# Sheet1.net
KiCad netlist of a schematic drawn in Altium Designer
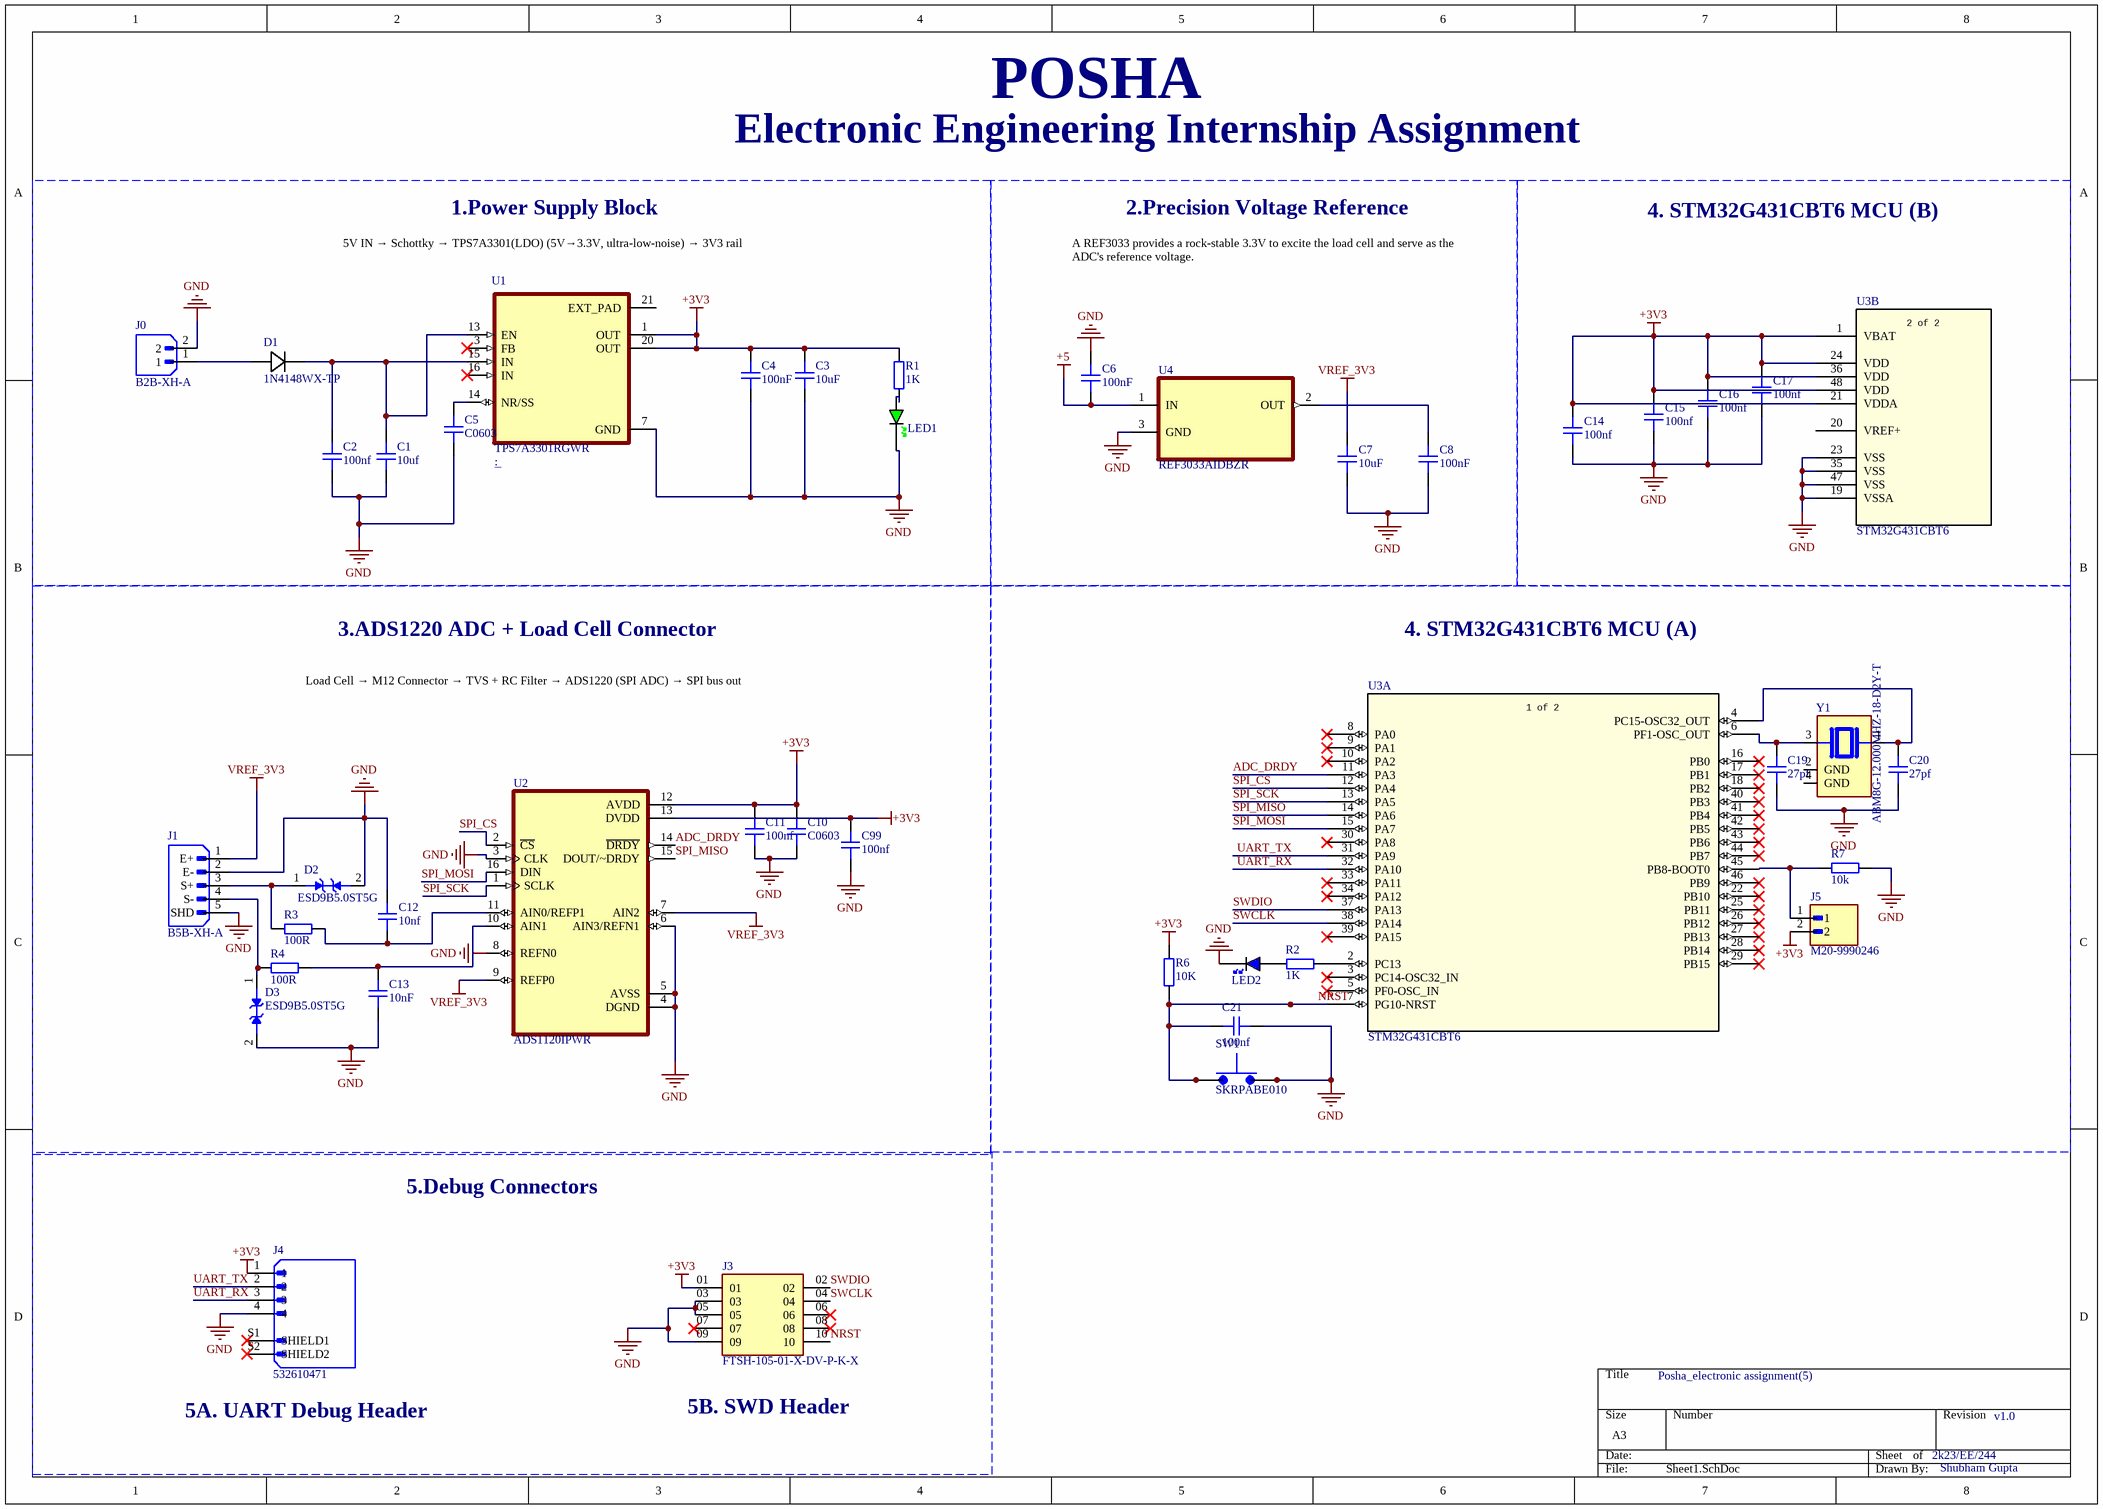
[diagram p0: Sheet1.SchDoc]

(export (version "E")
  (design (tool "Eeschema 10.0.6"))
  (components
    (comp (ref "C1")
      (value "10uf")
      (footprint "CAP_0805")
      (description "Capacitor SMD 0805")
      (libsource (lib "Schlib1") (part "CAP_0805"))
    )
    (comp (ref "C2")
      (value "100nf")
      (footprint "CAP_0603")
      (description "Capacitor SMD 0603")
      (libsource (lib "Schlib1") (part "CAP_0603"))
    )
    (comp (ref "C3")
      (value "10uF")
      (footprint "CAP_0603")
      (description "Capacitor SMD 0603")
      (libsource (lib "Schlib1") (part "CAP_0603"))
    )
    (comp (ref "C4")
      (value "100nF")
      (footprint "CAP_0805")
      (description "Capacitor SMD 0805")
      (libsource (lib "Schlib1") (part "CAP_0805"))
    )
    (comp (ref "C5")
      (value "C0603")
      (footprint "CAP_0603")
      (description "Capacitor SMD 0603")
      (libsource (lib "Schlib1") (part "CAP_0603"))
    )
    (comp (ref "C6")
      (value "100nF")
      (footprint "CAP_0603")
      (description "Capacitor SMD 0603")
      (libsource (lib "Schlib1") (part "CAP_0603"))
    )
    (comp (ref "C7")
      (value "10uF")
      (footprint "CAP_0805")
      (description "Capacitor SMD 0805")
      (libsource (lib "Schlib1") (part "CAP_0805"))
    )
    (comp (ref "C8")
      (value "100nF")
      (footprint "CAP_0603")
      (description "Capacitor SMD 0603")
      (libsource (lib "Schlib1") (part "CAP_0603"))
    )
    (comp (ref "C10")
      (value "C0603")
      (footprint "CAP_0603")
      (description "Capacitor SMD 0603")
      (libsource (lib "Schlib1") (part "CAP_0603"))
    )
    (comp (ref "C11")
      (value "100nf")
      (footprint "CAP_0603")
      (description "Capacitor SMD 0603")
      (libsource (lib "Schlib1") (part "CAP_0603"))
    )
    (comp (ref "C12")
      (value "10nf")
      (footprint "CAP_0603")
      (description "Capacitor SMD 0603")
      (libsource (lib "Schlib1") (part "CAP_0603"))
    )
    (comp (ref "C13")
      (value "10nF")
      (footprint "CAP_0603")
      (description "Capacitor SMD 0603")
      (libsource (lib "Schlib1") (part "CAP_0603"))
    )
    (comp (ref "C14")
      (value "100nf")
      (footprint "CAP_0603")
      (description "Capacitor SMD 0603")
      (libsource (lib "Schlib1") (part "CAP_0603"))
    )
    (comp (ref "C15")
      (value "100nf")
      (footprint "CAP_0603")
      (description "Capacitor SMD 0603")
      (libsource (lib "Schlib1") (part "CAP_0603"))
    )
    (comp (ref "C16")
      (value "100nf")
      (footprint "CAP_0603")
      (description "Capacitor SMD 0603")
      (libsource (lib "Schlib1") (part "CAP_0603"))
    )
    (comp (ref "C17")
      (value "100nf")
      (footprint "CAP_0603")
      (description "Capacitor SMD 0603")
      (libsource (lib "Schlib1") (part "CAP_0603"))
    )
    (comp (ref "C19")
      (value "27pf")
      (footprint "CAP_0603")
      (description "Capacitor SMD 0603")
      (libsource (lib "Schlib1") (part "CAP_0603"))
    )
    (comp (ref "C20")
      (value "27pf")
      (footprint "CAP_0603")
      (description "Capacitor SMD 0603")
      (libsource (lib "Schlib1") (part "CAP_0603"))
    )
    (comp (ref "C21")
      (value "100nf")
      (footprint "CAP_0603")
      (description "Capacitor SMD 0603")
      (libsource (lib "Schlib1") (part "CAP_0603"))
    )
    (comp (ref "C99")
      (value "100nf")
      (footprint "CAP_0603")
      (description "Capacitor SMD 0603")
      (libsource (lib "Schlib1") (part "CAP_0603"))
    )
    (comp (ref "D1")
      (value "1N4148WX-TP")
      (footprint "CR_SOD323_MCC")
      (description "Description")
      (fields (field (name "COPYRIGHT") "Copyright (C) 2025 Ultra Librarian. All rights reserved."))
      (libsource (lib "Schlib1") (part "1N4148WX-TP"))
    )
    (comp (ref "D2")
      (value "ESD9B5.0ST5G")
      (footprint "SODFL1006X40N")
      (description "Clamp Ipp Tvs Diode Surface Mount SOD-923")
      (fields (field (name "MF") "ON Semiconductor"))
      (libsource (lib "Schlib1") (part "ESD9B5.0ST5G"))
    )
    (comp (ref "D3")
      (value "ESD9B5.0ST5G")
      (footprint "SODFL1006X40N")
      (description "Clamp Ipp Tvs Diode Surface Mount SOD-923")
      (fields (field (name "MF") "ON Semiconductor"))
      (libsource (lib "Schlib1") (part "ESD9B5.0ST5G"))
    )
    (comp (ref "J0")
      (value "B2B-XH-A")
      (footprint "HARWIN_M20-9990246")
      (fields (field (name "MF") "{'manufacturer': u'JST Sales America Inc.'}"))
      (libsource (lib "Schlib1") (part "B2B-XH-A"))
    )
    (comp (ref "J1")
      (value "B5B-XH-A")
      (footprint "JST_B5B-XH-A")
      (description "Connector Header Through Hole 5 position 0.098 (2.50mm)")
      (fields (field (name "MF") "JST Sales"))
      (libsource (lib "Schlib1") (part "B5B-XH-A"))
    )
    (comp (ref "J3")
      (value "FTSH-105-01-X-DV-P-K-X")
      (footprint "SAMTEC_FTSH-105-01-X-DV-P-K-X")
      (fields (field (name "MF") "{'manufacturer': u'Samtec Inc.'}"))
      (libsource (lib "Schlib1") (part "FTSH-105-01-X-DV-P-K-X"))
    )
    (comp (ref "J4")
      (value "532610471")
      (footprint "MOLEX_532610471")
      (description "Connector Header Surface Mount, Right Angle 4 position 0.049 (1.25mm)")
      (fields (field (name "MF") "Molex"))
      (libsource (lib "Schlib1") (part "532610471"))
    )
    (comp (ref "J5")
      (value "M20-9990246")
      (footprint "HARWIN_M20-9990246")
      (description "2.54mm (0.1) Pitch SIL Vertical Throughboard Pin Header, 6.1mm mating pin height, tin, 2 contacts")
      (fields (field (name "MF") "Harwin"))
      (libsource (lib "Schlib1") (part "M20-9990246"))
    )
    (comp (ref "LED1")
      (value "GREEN")
      (footprint "LED_0603_GREEN")
      (description "LED 0603 GREEN SMD")
      (libsource (lib "Schlib1") (part "LED_0603_GREEN"))
    )
    (comp (ref "LED2")
      (value "BLUE")
      (footprint "LED_0402_BLUE")
      (description "LED 0402 BLUE SMD")
      (libsource (lib "Schlib1") (part "LED_0402_BLUE"))
    )
    (comp (ref "R1")
      (value "1K")
      (footprint "RES_0603")
      (description "Resistor SMD 0603")
      (libsource (lib "Schlib1") (part "RES_0603"))
    )
    (comp (ref "R2")
      (value "1K")
      (footprint "RES_0603")
      (description "Resistor SMD 0603")
      (libsource (lib "Schlib1") (part "RES_0603"))
    )
    (comp (ref "R3")
      (value "100R")
      (footprint "RES_0603")
      (description "Resistor SMD 0603")
      (libsource (lib "Schlib1") (part "RES_0603"))
    )
    (comp (ref "R4")
      (value "100R")
      (footprint "RES_0603")
      (description "Resistor SMD 0603")
      (libsource (lib "Schlib1") (part "RES_0603"))
    )
    (comp (ref "R6")
      (value "10K")
      (footprint "RES_0603")
      (description "Resistor SMD 0603")
      (libsource (lib "Schlib1") (part "RES_0603"))
    )
    (comp (ref "R7")
      (value "10k")
      (footprint "RES_0603")
      (description "Resistor SMD 0603")
      (libsource (lib "Schlib1") (part "RES_0603"))
    )
    (comp (ref "SW1")
      (value "SKRPABE010")
      (footprint "SW_SKRPABE010")
      (description "Switch Tactile N.O. SPST Button J-Bend 0.05A 16VDC 1.57N SMD Automotive T/R")
      (fields (field (name "MF") "ALPS"))
      (libsource (lib "Schlib1") (part "SKRPABE010"))
    )
    (comp (ref "U1")
      (value "TPS7A3301RGWR")
      (footprint "QFN65P500X500X100-21N")
      (description "1-A, high-PSRR, negative, adjustable low-dropout voltage regulator with enable 20-VQFN -40 to 125")
      (fields (field (name "DIGI-KEY_PART_NUMBER") "296-39502-1-ND") (field (name "MF") "Texas Instruments"))
      (libsource (lib "Schlib1") (part "TPS7A3301RGWR"))
    )
    (comp (ref "U2")
      (value "ADS1120IPWR")
      (footprint "SOP65P640X120-16N")
      (fields (field (name "MF") "Texas Instruments"))
      (libsource (lib "Schlib1") (part "ADS1120IPWR"))
    )
    (comp (ref "U3")
      (value "STM32G431CBT6")
      (footprint "LQFP48-7x7mm")
      (fields (field (name "COPYRIGHT") "Copyright (C) 2025 Ultra Librarian. All rights reserved."))
      (libsource (lib "Schlib1") (part "STM32G431CBT6"))
    )
    (comp (ref "U4")
      (value "REF3033AIDBZR")
      (footprint "SOT95P237X112-3N")
      (description "3.3-V, 50-ppm/Â°C, 50-ÂµA in 3-pin SOT-23 package series (bandgap) voltage reference")
      (fields (field (name "MF") "Texas Instruments"))
      (libsource (lib "Schlib1") (part "REF3033AIDBZR"))
    )
    (comp (ref "Y1")
      (value "ABM8G-12.000MHZ-18-D2Y-T")
      (footprint "XTAL_ABM8G-12.000MHZ-18-D2Y-T")
      (description "12 MHz Â±20ppm Crystal 18pF 120 Ohms 4-SMD, No Lead")
      (fields (field (name "DIGI-KEY_PART_NUMBER") "535-10261-2-ND") (field (name "MF") "Abracon"))
      (libsource (lib "Schlib1") (part "ABM8G-12.000MHZ-18-D2Y-T"))
    )
  )
  (nets
    (net (code "1") (name "+3V3") (class "Default")
      (node (ref "C10") (pin "2") (pinfunction "2_2") (pintype "passive"))
      (node (ref "C11") (pin "2") (pinfunction "2_2") (pintype "passive"))
      (node (ref "C14") (pin "2") (pinfunction "2_2") (pintype "passive"))
      (node (ref "C15") (pin "2") (pinfunction "2_2") (pintype "passive"))
      (node (ref "C16") (pin "2") (pinfunction "2_2") (pintype "passive"))
      (node (ref "C17") (pin "2") (pinfunction "2_2") (pintype "passive"))
      (node (ref "C3") (pin "2") (pinfunction "2_2") (pintype "passive"))
      (node (ref "C4") (pin "2") (pinfunction "2_2") (pintype "passive"))
      (node (ref "C99") (pin "2") (pinfunction "2_2") (pintype "passive"))
      (node (ref "J3") (pin "01") (pinfunction "01_01") (pintype "passive"))
      (node (ref "J4") (pin "1") (pinfunction "1_1") (pintype "passive"))
      (node (ref "J5") (pin "2") (pinfunction "2_2") (pintype "passive"))
      (node (ref "R1") (pin "2") (pinfunction "2_2") (pintype "passive"))
      (node (ref "R6") (pin "2") (pinfunction "2_2") (pintype "passive"))
      (node (ref "U1") (pin "1") (pinfunction "OUT_1") (pintype "passive"))
      (node (ref "U1") (pin "20") (pinfunction "OUT_20") (pintype "passive"))
      (node (ref "U2") (pin "12") (pinfunction "AVDD_12") (pintype "power_in"))
      (node (ref "U2") (pin "13") (pinfunction "DVDD_13") (pintype "power_in"))
      (node (ref "U3") (pin "1") (pinfunction "VBAT_1") (pintype "power_in"))
      (node (ref "U3") (pin "21") (pinfunction "VDDA_21") (pintype "power_in"))
      (node (ref "U3") (pin "24") (pinfunction "VDD_24") (pintype "power_in"))
      (node (ref "U3") (pin "36") (pinfunction "VDD_36") (pintype "power_in"))
      (node (ref "U3") (pin "48") (pinfunction "VDD_48") (pintype "power_in"))
    )
    (net (code "2") (name "+5") (class "Default")
      (node (ref "C6") (pin "1") (pinfunction "1_1") (pintype "passive"))
      (node (ref "U4") (pin "1") (pinfunction "IN_1") (pintype "power_in"))
    )
    (net (code "3") (name "/ADC_DRDY") (class "Default")
      (node (ref "U2") (pin "14") (pinfunction "~{DRDY}_14") (pintype "output"))
      (node (ref "U3") (pin "11") (pinfunction "PA3_11") (pintype "bidirectional"))
    )
    (net (code "4") (name "/NRST") (class "Default")
      (node (ref "C21") (pin "2") (pinfunction "2_2") (pintype "passive"))
      (node (ref "J3") (pin "10") (pinfunction "10_10") (pintype "passive"))
      (node (ref "R6") (pin "1") (pinfunction "1_1") (pintype "passive"))
      (node (ref "SW1") (pin "1") (pinfunction "1_1") (pintype "passive"))
      (node (ref "SW1") (pin "2") (pinfunction "1_2") (pintype "passive"))
      (node (ref "U3") (pin "7") (pinfunction "PG10-NRST_7") (pintype "bidirectional"))
    )
    (net (code "5") (name "/SPI_CS") (class "Default")
      (node (ref "U2") (pin "2") (pinfunction "~{CS}_2") (pintype "input"))
      (node (ref "U3") (pin "12") (pinfunction "PA4_12") (pintype "bidirectional"))
    )
    (net (code "6") (name "/SPI_MISO") (class "Default")
      (node (ref "U2") (pin "15") (pinfunction "DOUT/~DRDY_15") (pintype "output"))
      (node (ref "U3") (pin "14") (pinfunction "PA6_14") (pintype "bidirectional"))
    )
    (net (code "7") (name "/SPI_MOSI") (class "Default")
      (node (ref "U2") (pin "16") (pinfunction "DIN_16") (pintype "input"))
      (node (ref "U3") (pin "15") (pinfunction "PA7_15") (pintype "bidirectional"))
    )
    (net (code "8") (name "/SPI_SCK") (class "Default")
      (node (ref "U2") (pin "1") (pinfunction "SCLK_1") (pintype "input"))
      (node (ref "U3") (pin "13") (pinfunction "PA5_13") (pintype "bidirectional"))
    )
    (net (code "9") (name "/SWCLK") (class "Default")
      (node (ref "J3") (pin "04") (pinfunction "04_04") (pintype "passive"))
      (node (ref "U3") (pin "38") (pinfunction "PA14_38") (pintype "bidirectional"))
    )
    (net (code "10") (name "/SWDIO") (class "Default")
      (node (ref "J3") (pin "02") (pinfunction "02_02") (pintype "passive"))
      (node (ref "U3") (pin "37") (pinfunction "PA13_37") (pintype "bidirectional"))
    )
    (net (code "11") (name "/UART_RX") (class "Default")
      (node (ref "J4") (pin "3") (pinfunction "3_3") (pintype "passive"))
      (node (ref "U3") (pin "32") (pinfunction "PA10_32") (pintype "bidirectional"))
    )
    (net (code "12") (name "/UART_TX") (class "Default")
      (node (ref "J4") (pin "2") (pinfunction "2_2") (pintype "passive"))
      (node (ref "U3") (pin "31") (pinfunction "PA9_31") (pintype "bidirectional"))
    )
    (net (code "13") (name "GND") (class "Default")
      (node (ref "C1") (pin "1") (pinfunction "1_1") (pintype "passive"))
      (node (ref "C10") (pin "1") (pinfunction "1_1") (pintype "passive"))
      (node (ref "C11") (pin "1") (pinfunction "1_1") (pintype "passive"))
      (node (ref "C12") (pin "2") (pinfunction "2_2") (pintype "passive"))
      (node (ref "C13") (pin "1") (pinfunction "1_1") (pintype "passive"))
      (node (ref "C14") (pin "1") (pinfunction "1_1") (pintype "passive"))
      (node (ref "C15") (pin "1") (pinfunction "1_1") (pintype "passive"))
      (node (ref "C16") (pin "1") (pinfunction "1_1") (pintype "passive"))
      (node (ref "C17") (pin "1") (pinfunction "1_1") (pintype "passive"))
      (node (ref "C19") (pin "2") (pinfunction "2_2") (pintype "passive"))
      (node (ref "C2") (pin "1") (pinfunction "1_1") (pintype "passive"))
      (node (ref "C20") (pin "2") (pinfunction "2_2") (pintype "passive"))
      (node (ref "C21") (pin "1") (pinfunction "1_1") (pintype "passive"))
      (node (ref "C3") (pin "1") (pinfunction "1_1") (pintype "passive"))
      (node (ref "C4") (pin "1") (pinfunction "1_1") (pintype "passive"))
      (node (ref "C5") (pin "1") (pinfunction "1_1") (pintype "passive"))
      (node (ref "C6") (pin "2") (pinfunction "2_2") (pintype "passive"))
      (node (ref "C7") (pin "1") (pinfunction "1_1") (pintype "passive"))
      (node (ref "C8") (pin "1") (pinfunction "1_1") (pintype "passive"))
      (node (ref "C99") (pin "1") (pinfunction "1_1") (pintype "passive"))
      (node (ref "D2") (pin "2") (pinfunction "A1_2") (pintype "passive"))
      (node (ref "D3") (pin "2") (pinfunction "A1_2") (pintype "passive"))
      (node (ref "J0") (pin "2") (pinfunction "2_2") (pintype "passive"))
      (node (ref "J1") (pin "2") (pinfunction "E-_2") (pintype "passive"))
      (node (ref "J1") (pin "5") (pinfunction "SHD_5") (pintype "passive"))
      (node (ref "J3") (pin "03") (pinfunction "03_03") (pintype "passive"))
      (node (ref "J3") (pin "05") (pinfunction "05_05") (pintype "passive"))
      (node (ref "J3") (pin "09") (pinfunction "09_09") (pintype "passive"))
      (node (ref "J4") (pin "4") (pinfunction "4_4") (pintype "passive"))
      (node (ref "LED1") (pin "K") (pinfunction "K_K") (pintype "passive"))
      (node (ref "LED2") (pin "K") (pinfunction "K_K") (pintype "passive"))
      (node (ref "R7") (pin "1") (pinfunction "1_1") (pintype "passive"))
      (node (ref "SW1") (pin "3") (pinfunction "2_3") (pintype "passive"))
      (node (ref "SW1") (pin "4") (pinfunction "2_4") (pintype "passive"))
      (node (ref "U1") (pin "7") (pinfunction "GND_7") (pintype "power_in"))
      (node (ref "U2") (pin "3") (pinfunction "CLK_3") (pintype "input"))
      (node (ref "U2") (pin "4") (pinfunction "DGND_4") (pintype "power_in"))
      (node (ref "U2") (pin "5") (pinfunction "AVSS_5") (pintype "power_in"))
      (node (ref "U2") (pin "6") (pinfunction "AIN3/REFN1_6") (pintype "bidirectional"))
      (node (ref "U2") (pin "8") (pinfunction "REFN0_8") (pintype "bidirectional"))
      (node (ref "U3") (pin "19") (pinfunction "VSSA_19") (pintype "power_in"))
      (node (ref "U3") (pin "23") (pinfunction "VSS_23") (pintype "power_in"))
      (node (ref "U3") (pin "35") (pinfunction "VSS_35") (pintype "power_in"))
      (node (ref "U3") (pin "47") (pinfunction "VSS_47") (pintype "power_in"))
      (node (ref "U4") (pin "3") (pinfunction "GND_3") (pintype "passive"))
    )
    (net (code "14") (name "Net-(D1-Pad2)") (class "Default")
      (node (ref "D1") (pin "2") (pinfunction "2_2") (pintype "passive"))
      (node (ref "J0") (pin "1") (pinfunction "1_1") (pintype "passive"))
    )
    (net (code "15") (name "Net-(D2-A)") (class "Default")
      (node (ref "D2") (pin "1") (pinfunction "A_1") (pintype "passive"))
      (node (ref "J1") (pin "3") (pinfunction "S+_3") (pintype "passive"))
      (node (ref "R3") (pin "2") (pinfunction "2_2") (pintype "passive"))
    )
    (net (code "16") (name "Net-(D3-A)") (class "Default")
      (node (ref "D3") (pin "1") (pinfunction "A_1") (pintype "passive"))
      (node (ref "J1") (pin "4") (pinfunction "S-_4") (pintype "passive"))
      (node (ref "R4") (pin "2") (pinfunction "2_2") (pintype "passive"))
    )
    (net (code "17") (name "Net-(LED1-PadA)") (class "Default")
      (node (ref "LED1") (pin "A") (pinfunction "A_A") (pintype "passive"))
      (node (ref "R1") (pin "1") (pinfunction "1_1") (pintype "passive"))
    )
    (net (code "18") (name "Net-(LED2-PadA)") (class "Default")
      (node (ref "LED2") (pin "A") (pinfunction "A_A") (pintype "passive"))
      (node (ref "R2") (pin "2") (pinfunction "2_2") (pintype "passive"))
    )
    (net (code "19") (name "Net-(U1-EN)") (class "Default")
      (node (ref "C1") (pin "2") (pinfunction "2_2") (pintype "passive"))
      (node (ref "C2") (pin "2") (pinfunction "2_2") (pintype "passive"))
      (node (ref "D1") (pin "1") (pinfunction "1_1") (pintype "passive"))
      (node (ref "U1") (pin "13") (pinfunction "EN_13") (pintype "input"))
      (node (ref "U1") (pin "15") (pinfunction "IN_15") (pintype "input"))
    )
    (net (code "20") (name "Net-(U1-NR{slash}SS)") (class "Default")
      (node (ref "C5") (pin "2") (pinfunction "2_2") (pintype "passive"))
      (node (ref "U1") (pin "14") (pinfunction "NR/SS_14") (pintype "bidirectional"))
    )
    (net (code "21") (name "Net-(U2-AIN0{slash}REFP1)") (class "Default")
      (node (ref "C12") (pin "1") (pinfunction "1_1") (pintype "passive"))
      (node (ref "R3") (pin "1") (pinfunction "1_1") (pintype "passive"))
      (node (ref "U2") (pin "11") (pinfunction "AIN0/REFP1_11") (pintype "bidirectional"))
    )
    (net (code "22") (name "Net-(U2-AIN1)") (class "Default")
      (node (ref "C13") (pin "2") (pinfunction "2_2") (pintype "passive"))
      (node (ref "R4") (pin "1") (pinfunction "1_1") (pintype "passive"))
      (node (ref "U2") (pin "10") (pinfunction "AIN1_10") (pintype "bidirectional"))
    )
    (net (code "23") (name "Net-(U3A-PB8-BOOT0)") (class "Default")
      (node (ref "J5") (pin "1") (pinfunction "1_1") (pintype "passive"))
      (node (ref "R7") (pin "2") (pinfunction "2_2") (pintype "passive"))
      (node (ref "U3") (pin "45") (pinfunction "PB8-BOOT0_45") (pintype "bidirectional"))
    )
    (net (code "24") (name "Net-(U3A-PC13)") (class "Default")
      (node (ref "R2") (pin "1") (pinfunction "1_1") (pintype "passive"))
      (node (ref "U3") (pin "2") (pinfunction "PC13_2") (pintype "bidirectional"))
    )
    (net (code "25") (name "Net-(U3A-PC15-OSC32_OUT)") (class "Default")
      (node (ref "C20") (pin "1") (pinfunction "1_1") (pintype "passive"))
      (node (ref "U3") (pin "4") (pinfunction "PC15-OSC32_OUT_4") (pintype "bidirectional"))
      (node (ref "Y1") (pin "1") (pinfunction "1_1") (pintype "passive"))
    )
    (net (code "26") (name "Net-(U3A-PF1-OSC_OUT)") (class "Default")
      (node (ref "C19") (pin "1") (pinfunction "1_1") (pintype "passive"))
      (node (ref "U3") (pin "6") (pinfunction "PF1-OSC_OUT_6") (pintype "bidirectional"))
      (node (ref "Y1") (pin "3") (pinfunction "2_3") (pintype "passive"))
    )
    (net (code "27") (name "Net-(U4-OUT)") (class "Default")
      (node (ref "C8") (pin "2") (pinfunction "2_2") (pintype "passive"))
      (node (ref "U4") (pin "2") (pinfunction "OUT_2") (pintype "output"))
    )
    (net (code "28") (name "VREF_3V3") (class "Default")
      (node (ref "C7") (pin "2") (pinfunction "2_2") (pintype "passive"))
      (node (ref "J1") (pin "1") (pinfunction "E+_1") (pintype "passive"))
      (node (ref "U2") (pin "7") (pinfunction "AIN2_7") (pintype "bidirectional"))
      (node (ref "U2") (pin "9") (pinfunction "REFP0_9") (pintype "bidirectional"))
    )
    (net (code "29") (name "unconnected-(J3-Pad06)") (class "Default")
      (node (ref "J3") (pin "06") (pinfunction "06_06") (pintype "passive+no_connect"))
    )
    (net (code "30") (name "unconnected-(J3-Pad07)") (class "Default")
      (node (ref "J3") (pin "07") (pinfunction "07_07") (pintype "passive"))
    )
    (net (code "31") (name "unconnected-(J3-Pad08)") (class "Default")
      (node (ref "J3") (pin "08") (pinfunction "08_08") (pintype "passive+no_connect"))
    )
    (net (code "32") (name "unconnected-(J4-SHIELD1-PadS1)") (class "Default")
      (node (ref "J4") (pin "S1") (pinfunction "SHIELD1_S1") (pintype "passive+no_connect"))
    )
    (net (code "33") (name "unconnected-(J4-SHIELD2-PadS2)") (class "Default")
      (node (ref "J4") (pin "S2") (pinfunction "SHIELD2_S2") (pintype "passive+no_connect"))
    )
    (net (code "34") (name "unconnected-(U1-EXT_PAD-Pad21)") (class "Default")
      (node (ref "U1") (pin "21") (pinfunction "EXT_PAD_21") (pintype "power_in"))
    )
    (net (code "35") (name "unconnected-(U1-FB-Pad3)") (class "Default")
      (node (ref "U1") (pin "3") (pinfunction "FB_3") (pintype "input+no_connect"))
    )
    (net (code "36") (name "unconnected-(U1-IN-Pad16)") (class "Default")
      (node (ref "U1") (pin "16") (pinfunction "IN_16") (pintype "input+no_connect"))
    )
    (net (code "37") (name "unconnected-(U3A-PA0-Pad8)") (class "Default")
      (node (ref "U3") (pin "8") (pinfunction "PA0_8") (pintype "bidirectional+no_connect"))
    )
    (net (code "38") (name "unconnected-(U3A-PA1-Pad9)") (class "Default")
      (node (ref "U3") (pin "9") (pinfunction "PA1_9") (pintype "bidirectional+no_connect"))
    )
    (net (code "39") (name "unconnected-(U3A-PA2-Pad10)") (class "Default")
      (node (ref "U3") (pin "10") (pinfunction "PA2_10") (pintype "bidirectional+no_connect"))
    )
    (net (code "40") (name "unconnected-(U3A-PA8-Pad30)") (class "Default")
      (node (ref "U3") (pin "30") (pinfunction "PA8_30") (pintype "bidirectional+no_connect"))
    )
    (net (code "41") (name "unconnected-(U3A-PA11-Pad33)") (class "Default")
      (node (ref "U3") (pin "33") (pinfunction "PA11_33") (pintype "bidirectional+no_connect"))
    )
    (net (code "42") (name "unconnected-(U3A-PA12-Pad34)") (class "Default")
      (node (ref "U3") (pin "34") (pinfunction "PA12_34") (pintype "bidirectional+no_connect"))
    )
    (net (code "43") (name "unconnected-(U3A-PA15-Pad39)") (class "Default")
      (node (ref "U3") (pin "39") (pinfunction "PA15_39") (pintype "bidirectional+no_connect"))
    )
    (net (code "44") (name "unconnected-(U3A-PB0-Pad16)") (class "Default")
      (node (ref "U3") (pin "16") (pinfunction "PB0_16") (pintype "bidirectional+no_connect"))
    )
    (net (code "45") (name "unconnected-(U3A-PB1-Pad17)") (class "Default")
      (node (ref "U3") (pin "17") (pinfunction "PB1_17") (pintype "bidirectional+no_connect"))
    )
    (net (code "46") (name "unconnected-(U3A-PB2-Pad18)") (class "Default")
      (node (ref "U3") (pin "18") (pinfunction "PB2_18") (pintype "bidirectional+no_connect"))
    )
    (net (code "47") (name "unconnected-(U3A-PB3-Pad40)") (class "Default")
      (node (ref "U3") (pin "40") (pinfunction "PB3_40") (pintype "bidirectional+no_connect"))
    )
    (net (code "48") (name "unconnected-(U3A-PB4-Pad41)") (class "Default")
      (node (ref "U3") (pin "41") (pinfunction "PB4_41") (pintype "bidirectional+no_connect"))
    )
    (net (code "49") (name "unconnected-(U3A-PB5-Pad42)") (class "Default")
      (node (ref "U3") (pin "42") (pinfunction "PB5_42") (pintype "bidirectional+no_connect"))
    )
    (net (code "50") (name "unconnected-(U3A-PB6-Pad43)") (class "Default")
      (node (ref "U3") (pin "43") (pinfunction "PB6_43") (pintype "bidirectional+no_connect"))
    )
    (net (code "51") (name "unconnected-(U3A-PB7-Pad44)") (class "Default")
      (node (ref "U3") (pin "44") (pinfunction "PB7_44") (pintype "bidirectional+no_connect"))
    )
    (net (code "52") (name "unconnected-(U3A-PB9-Pad46)") (class "Default")
      (node (ref "U3") (pin "46") (pinfunction "PB9_46") (pintype "bidirectional+no_connect"))
    )
    (net (code "53") (name "unconnected-(U3A-PB10-Pad22)") (class "Default")
      (node (ref "U3") (pin "22") (pinfunction "PB10_22") (pintype "bidirectional+no_connect"))
    )
    (net (code "54") (name "unconnected-(U3A-PB11-Pad25)") (class "Default")
      (node (ref "U3") (pin "25") (pinfunction "PB11_25") (pintype "bidirectional+no_connect"))
    )
    (net (code "55") (name "unconnected-(U3A-PB12-Pad26)") (class "Default")
      (node (ref "U3") (pin "26") (pinfunction "PB12_26") (pintype "bidirectional+no_connect"))
    )
    (net (code "56") (name "unconnected-(U3A-PB13-Pad27)") (class "Default")
      (node (ref "U3") (pin "27") (pinfunction "PB13_27") (pintype "bidirectional+no_connect"))
    )
    (net (code "57") (name "unconnected-(U3A-PB14-Pad28)") (class "Default")
      (node (ref "U3") (pin "28") (pinfunction "PB14_28") (pintype "bidirectional+no_connect"))
    )
    (net (code "58") (name "unconnected-(U3A-PB15-Pad29)") (class "Default")
      (node (ref "U3") (pin "29") (pinfunction "PB15_29") (pintype "bidirectional+no_connect"))
    )
    (net (code "59") (name "unconnected-(U3A-PC14-OSC32_IN-Pad3)") (class "Default")
      (node (ref "U3") (pin "3") (pinfunction "PC14-OSC32_IN_3") (pintype "bidirectional+no_connect"))
    )
    (net (code "60") (name "unconnected-(U3A-PF0-OSC_IN-Pad5)") (class "Default")
      (node (ref "U3") (pin "5") (pinfunction "PF0-OSC_IN_5") (pintype "bidirectional+no_connect"))
    )
    (net (code "61") (name "unconnected-(U3B-VREF+-Pad20)") (class "Default")
      (node (ref "U3") (pin "20") (pinfunction "VREF+_20") (pintype "power_in"))
    )
    (net (code "62") (name "unconnected-(Y1-GND-Pad2)") (class "Default")
      (node (ref "Y1") (pin "2") (pinfunction "GND_2") (pintype "power_in"))
    )
    (net (code "63") (name "unconnected-(Y1-GND-Pad4)") (class "Default")
      (node (ref "Y1") (pin "4") (pinfunction "GND_4") (pintype "power_in"))
    )
  )
)
